# me433_2019_pic32.net
KiCad netlist of a schematic drawn in EAGLE
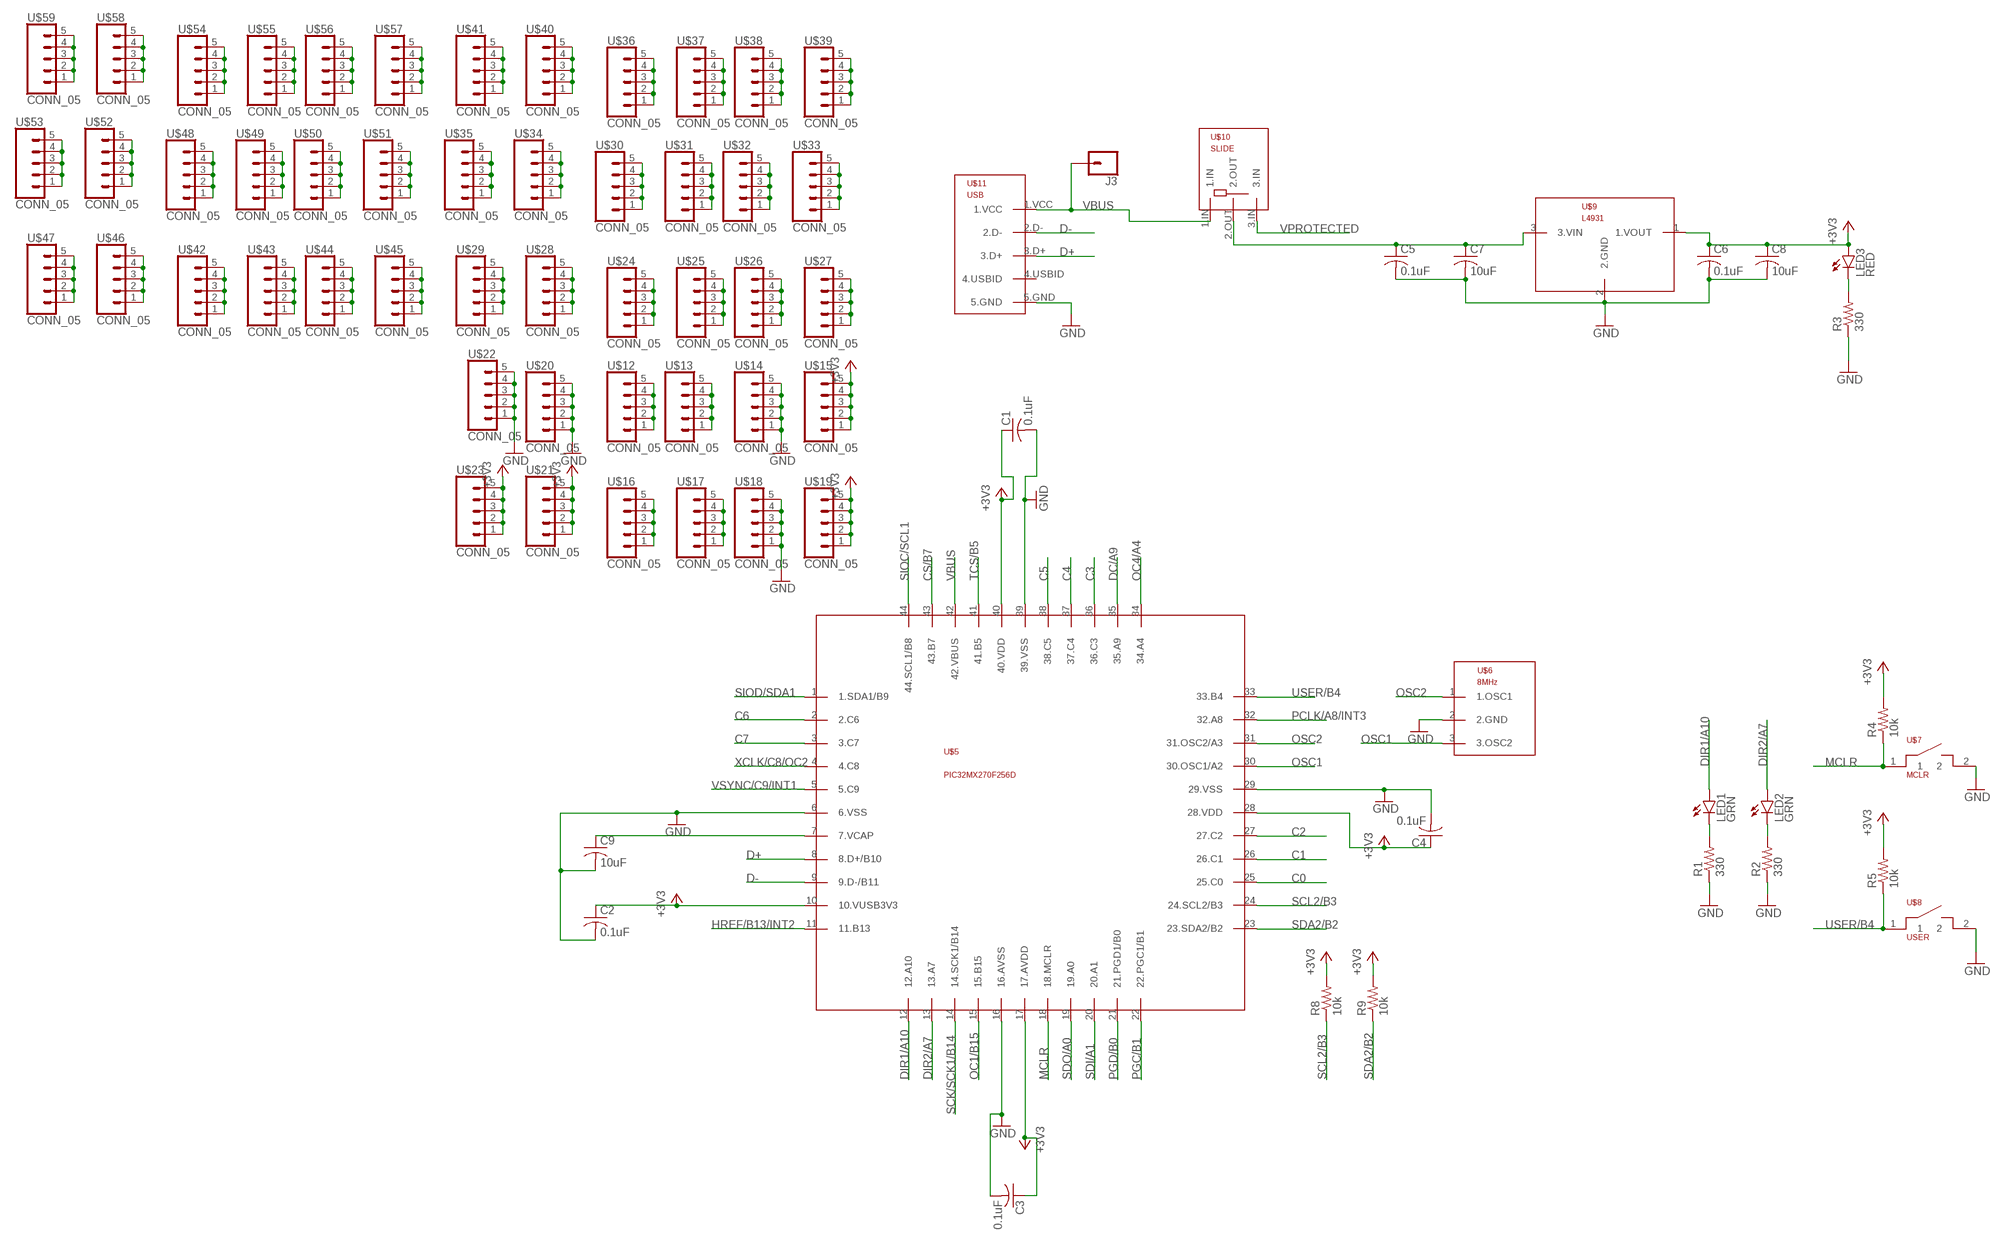
[diagram p0: schematic, sheet 1, part 1 of 2]
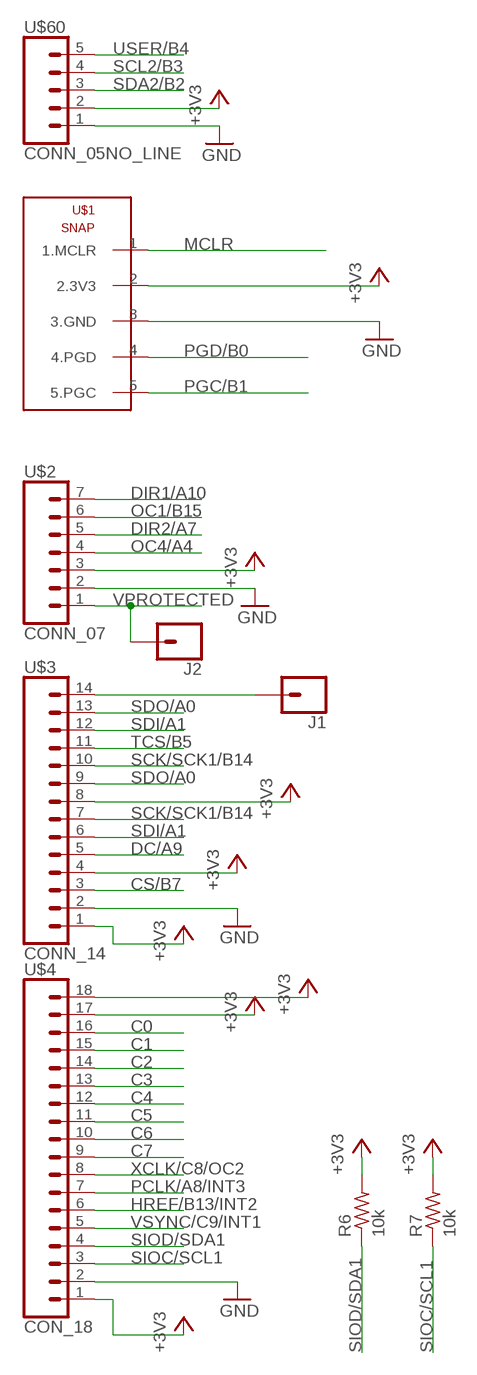
[diagram p1: schematic, sheet 1, part 2 of 2]

(export (version "E")
  (design (tool "Eeschema 10.0.6"))
  (components
    (comp (ref "C1")
      (value "0.1uF")
      (footprint "eagle-import:C025-030X050")
      (libsource (lib "eagle-import") (part "C-US025-030X050"))
    )
    (comp (ref "C2")
      (value "0.1uF")
      (footprint "eagle-import:C025-030X050")
      (libsource (lib "eagle-import") (part "C-US025-030X050"))
    )
    (comp (ref "C3")
      (value "0.1uF")
      (footprint "eagle-import:C025-030X050")
      (libsource (lib "eagle-import") (part "C-US025-030X050"))
    )
    (comp (ref "C4")
      (value "0.1uF")
      (footprint "eagle-import:C025-030X050")
      (libsource (lib "eagle-import") (part "C-US025-030X050"))
    )
    (comp (ref "C5")
      (value "0.1uF")
      (footprint "eagle-import:C025-030X050")
      (libsource (lib "eagle-import") (part "C-US025-030X050"))
    )
    (comp (ref "C6")
      (value "0.1uF")
      (footprint "eagle-import:C025-030X050")
      (libsource (lib "eagle-import") (part "C-US025-030X050"))
    )
    (comp (ref "C7")
      (value "10uF")
      (footprint "eagle-import:C025-030X050")
      (libsource (lib "eagle-import") (part "C-US025-030X050"))
    )
    (comp (ref "C8")
      (value "10uF")
      (footprint "eagle-import:C025-030X050")
      (libsource (lib "eagle-import") (part "C-US025-030X050"))
    )
    (comp (ref "C9")
      (value "10uF")
      (footprint "eagle-import:C025-030X050")
      (libsource (lib "eagle-import") (part "C-US025-030X050"))
    )
    (comp (ref "J1")
      (value "CONN_01")
      (footprint "eagle-import:1X01")
      (libsource (lib "eagle-import") (part "CONN_01"))
    )
    (comp (ref "J2")
      (value "CONN_01")
      (footprint "eagle-import:1X01")
      (libsource (lib "eagle-import") (part "CONN_01"))
    )
    (comp (ref "J3")
      (value "CONN_01")
      (footprint "eagle-import:1X01")
      (libsource (lib "eagle-import") (part "CONN_01"))
    )
    (comp (ref "LED1")
      (value "GRN")
      (footprint "eagle-import:LED3MM")
      (libsource (lib "eagle-import") (part "LED3MM"))
    )
    (comp (ref "LED2")
      (value "GRN")
      (footprint "eagle-import:LED3MM")
      (libsource (lib "eagle-import") (part "LED3MM"))
    )
    (comp (ref "LED3")
      (value "RED")
      (footprint "eagle-import:LED3MM")
      (libsource (lib "eagle-import") (part "LED3MM"))
    )
    (comp (ref "R1")
      (value "330")
      (footprint "eagle-import:0207_10")
      (libsource (lib "eagle-import") (part "R-US_0207/10"))
    )
    (comp (ref "R2")
      (value "330")
      (footprint "eagle-import:0207_10")
      (libsource (lib "eagle-import") (part "R-US_0207/10"))
    )
    (comp (ref "R3")
      (value "330")
      (footprint "eagle-import:0207_10")
      (libsource (lib "eagle-import") (part "R-US_0207/10"))
    )
    (comp (ref "R4")
      (value "10k")
      (footprint "eagle-import:0207_10")
      (libsource (lib "eagle-import") (part "R-US_0207/10"))
    )
    (comp (ref "R5")
      (value "10k")
      (footprint "eagle-import:0207_10")
      (libsource (lib "eagle-import") (part "R-US_0207/10"))
    )
    (comp (ref "R6")
      (value "10k")
      (footprint "eagle-import:0207_10")
      (libsource (lib "eagle-import") (part "R-US_0207/10"))
    )
    (comp (ref "R7")
      (value "10k")
      (footprint "eagle-import:0207_10")
      (libsource (lib "eagle-import") (part "R-US_0207/10"))
    )
    (comp (ref "R8")
      (value "10k")
      (footprint "eagle-import:0207_10")
      (libsource (lib "eagle-import") (part "R-US_0207/10"))
    )
    (comp (ref "R9")
      (value "10k")
      (footprint "eagle-import:0207_10")
      (libsource (lib "eagle-import") (part "R-US_0207/10"))
    )
    (comp (ref "U$1")
      (value "SNAP")
      (footprint "eagle-import:SNAP")
      (libsource (lib "eagle-import") (part "SNAPSNAP"))
    )
    (comp (ref "U$2")
      (value "CONN_07")
      (footprint "eagle-import:1X07")
      (libsource (lib "eagle-import") (part "CONN_07"))
    )
    (comp (ref "U$3")
      (value "CONN_14")
      (footprint "eagle-import:1X14")
      (libsource (lib "eagle-import") (part "CONN_14"))
    )
    (comp (ref "U$4")
      (value "CON_18")
      (footprint "eagle-import:1X18")
      (libsource (lib "eagle-import") (part "CON_18"))
    )
    (comp (ref "U$5")
      (value "PIC32MX270F256D")
      (footprint "eagle-import:TQFP44")
      (libsource (lib "eagle-import") (part "PIC32MX270F256D"))
    )
    (comp (ref "U$6")
      (value "8MHz")
      (footprint "eagle-import:OSC")
      (libsource (lib "eagle-import") (part "OSC"))
    )
    (comp (ref "U$7")
      (value "MCLR")
      (footprint "eagle-import:PB")
      (libsource (lib "eagle-import") (part "PB"))
    )
    (comp (ref "U$8")
      (value "USER")
      (footprint "eagle-import:PB")
      (libsource (lib "eagle-import") (part "PB"))
    )
    (comp (ref "U$9")
      (value "L4931")
      (footprint "eagle-import:L4931")
      (libsource (lib "eagle-import") (part "L4931"))
    )
    (comp (ref "U$10")
      (value "SLIDE")
      (footprint "eagle-import:SLIDE")
      (libsource (lib "eagle-import") (part "SLIDE"))
    )
    (comp (ref "U$11")
      (value "USB")
      (footprint "eagle-import:USB")
      (libsource (lib "eagle-import") (part "USB"))
    )
    (comp (ref "U$12")
      (value "CONN_05")
      (footprint "eagle-import:1X05")
      (libsource (lib "eagle-import") (part "CONN_05"))
    )
    (comp (ref "U$13")
      (value "CONN_05")
      (footprint "eagle-import:1X05")
      (libsource (lib "eagle-import") (part "CONN_05"))
    )
    (comp (ref "U$14")
      (value "CONN_05")
      (footprint "eagle-import:1X05")
      (libsource (lib "eagle-import") (part "CONN_05"))
    )
    (comp (ref "U$15")
      (value "CONN_05")
      (footprint "eagle-import:1X05")
      (libsource (lib "eagle-import") (part "CONN_05"))
    )
    (comp (ref "U$16")
      (value "CONN_05")
      (footprint "eagle-import:1X05")
      (libsource (lib "eagle-import") (part "CONN_05"))
    )
    (comp (ref "U$17")
      (value "CONN_05")
      (footprint "eagle-import:1X05")
      (libsource (lib "eagle-import") (part "CONN_05"))
    )
    (comp (ref "U$18")
      (value "CONN_05")
      (footprint "eagle-import:1X05")
      (libsource (lib "eagle-import") (part "CONN_05"))
    )
    (comp (ref "U$19")
      (value "CONN_05")
      (footprint "eagle-import:1X05")
      (libsource (lib "eagle-import") (part "CONN_05"))
    )
    (comp (ref "U$20")
      (value "CONN_05")
      (footprint "eagle-import:1X05")
      (libsource (lib "eagle-import") (part "CONN_05"))
    )
    (comp (ref "U$21")
      (value "CONN_05")
      (footprint "eagle-import:1X05")
      (libsource (lib "eagle-import") (part "CONN_05"))
    )
    (comp (ref "U$22")
      (value "CONN_05")
      (footprint "eagle-import:1X05")
      (libsource (lib "eagle-import") (part "CONN_05"))
    )
    (comp (ref "U$23")
      (value "CONN_05")
      (footprint "eagle-import:1X05")
      (libsource (lib "eagle-import") (part "CONN_05"))
    )
    (comp (ref "U$24")
      (value "CONN_05")
      (footprint "eagle-import:1X05")
      (libsource (lib "eagle-import") (part "CONN_05"))
    )
    (comp (ref "U$25")
      (value "CONN_05")
      (footprint "eagle-import:1X05")
      (libsource (lib "eagle-import") (part "CONN_05"))
    )
    (comp (ref "U$26")
      (value "CONN_05")
      (footprint "eagle-import:1X05")
      (libsource (lib "eagle-import") (part "CONN_05"))
    )
    (comp (ref "U$27")
      (value "CONN_05")
      (footprint "eagle-import:1X05")
      (libsource (lib "eagle-import") (part "CONN_05"))
    )
    (comp (ref "U$28")
      (value "CONN_05")
      (footprint "eagle-import:1X05")
      (libsource (lib "eagle-import") (part "CONN_05"))
    )
    (comp (ref "U$29")
      (value "CONN_05")
      (footprint "eagle-import:1X05")
      (libsource (lib "eagle-import") (part "CONN_05"))
    )
    (comp (ref "U$30")
      (value "CONN_05")
      (footprint "eagle-import:1X05")
      (libsource (lib "eagle-import") (part "CONN_05"))
    )
    (comp (ref "U$31")
      (value "CONN_05")
      (footprint "eagle-import:1X05")
      (libsource (lib "eagle-import") (part "CONN_05"))
    )
    (comp (ref "U$32")
      (value "CONN_05")
      (footprint "eagle-import:1X05")
      (libsource (lib "eagle-import") (part "CONN_05"))
    )
    (comp (ref "U$33")
      (value "CONN_05")
      (footprint "eagle-import:1X05")
      (libsource (lib "eagle-import") (part "CONN_05"))
    )
    (comp (ref "U$34")
      (value "CONN_05")
      (footprint "eagle-import:1X05")
      (libsource (lib "eagle-import") (part "CONN_05"))
    )
    (comp (ref "U$35")
      (value "CONN_05")
      (footprint "eagle-import:1X05")
      (libsource (lib "eagle-import") (part "CONN_05"))
    )
    (comp (ref "U$36")
      (value "CONN_05")
      (footprint "eagle-import:1X05")
      (libsource (lib "eagle-import") (part "CONN_05"))
    )
    (comp (ref "U$37")
      (value "CONN_05")
      (footprint "eagle-import:1X05")
      (libsource (lib "eagle-import") (part "CONN_05"))
    )
    (comp (ref "U$38")
      (value "CONN_05")
      (footprint "eagle-import:1X05")
      (libsource (lib "eagle-import") (part "CONN_05"))
    )
    (comp (ref "U$39")
      (value "CONN_05")
      (footprint "eagle-import:1X05")
      (libsource (lib "eagle-import") (part "CONN_05"))
    )
    (comp (ref "U$40")
      (value "CONN_05")
      (footprint "eagle-import:1X05")
      (libsource (lib "eagle-import") (part "CONN_05"))
    )
    (comp (ref "U$41")
      (value "CONN_05")
      (footprint "eagle-import:1X05")
      (libsource (lib "eagle-import") (part "CONN_05"))
    )
    (comp (ref "U$42")
      (value "CONN_05")
      (footprint "eagle-import:1X05")
      (libsource (lib "eagle-import") (part "CONN_05"))
    )
    (comp (ref "U$43")
      (value "CONN_05")
      (footprint "eagle-import:1X05")
      (libsource (lib "eagle-import") (part "CONN_05"))
    )
    (comp (ref "U$44")
      (value "CONN_05")
      (footprint "eagle-import:1X05")
      (libsource (lib "eagle-import") (part "CONN_05"))
    )
    (comp (ref "U$45")
      (value "CONN_05")
      (footprint "eagle-import:1X05")
      (libsource (lib "eagle-import") (part "CONN_05"))
    )
    (comp (ref "U$46")
      (value "CONN_05")
      (footprint "eagle-import:1X05")
      (libsource (lib "eagle-import") (part "CONN_05"))
    )
    (comp (ref "U$47")
      (value "CONN_05")
      (footprint "eagle-import:1X05")
      (libsource (lib "eagle-import") (part "CONN_05"))
    )
    (comp (ref "U$48")
      (value "CONN_05")
      (footprint "eagle-import:1X05")
      (libsource (lib "eagle-import") (part "CONN_05"))
    )
    (comp (ref "U$49")
      (value "CONN_05")
      (footprint "eagle-import:1X05")
      (libsource (lib "eagle-import") (part "CONN_05"))
    )
    (comp (ref "U$50")
      (value "CONN_05")
      (footprint "eagle-import:1X05")
      (libsource (lib "eagle-import") (part "CONN_05"))
    )
    (comp (ref "U$51")
      (value "CONN_05")
      (footprint "eagle-import:1X05")
      (libsource (lib "eagle-import") (part "CONN_05"))
    )
    (comp (ref "U$52")
      (value "CONN_05")
      (footprint "eagle-import:1X05")
      (libsource (lib "eagle-import") (part "CONN_05"))
    )
    (comp (ref "U$53")
      (value "CONN_05")
      (footprint "eagle-import:1X05")
      (libsource (lib "eagle-import") (part "CONN_05"))
    )
    (comp (ref "U$54")
      (value "CONN_05")
      (footprint "eagle-import:1X05")
      (libsource (lib "eagle-import") (part "CONN_05"))
    )
    (comp (ref "U$55")
      (value "CONN_05")
      (footprint "eagle-import:1X05")
      (libsource (lib "eagle-import") (part "CONN_05"))
    )
    (comp (ref "U$56")
      (value "CONN_05")
      (footprint "eagle-import:1X05")
      (libsource (lib "eagle-import") (part "CONN_05"))
    )
    (comp (ref "U$57")
      (value "CONN_05")
      (footprint "eagle-import:1X05")
      (libsource (lib "eagle-import") (part "CONN_05"))
    )
    (comp (ref "U$58")
      (value "CONN_05")
      (footprint "eagle-import:1X05")
      (libsource (lib "eagle-import") (part "CONN_05"))
    )
    (comp (ref "U$59")
      (value "CONN_05")
      (footprint "eagle-import:1X05")
      (libsource (lib "eagle-import") (part "CONN_05"))
    )
    (comp (ref "U$60")
      (value "CONN_05NO_LINE")
      (footprint "eagle-import:1X05_NO_LINE")
      (libsource (lib "eagle-import") (part "CONN_05NO_LINE"))
    )
  )
  (nets
    (net (code "1") (name "+3V3") (class "Default")
      (node (ref "C1") (pin "1") (pinfunction "1_1") (pintype "passive"))
      (node (ref "C2") (pin "1") (pinfunction "1_1") (pintype "passive"))
      (node (ref "C3") (pin "1") (pinfunction "1_1") (pintype "passive"))
      (node (ref "C4") (pin "1") (pinfunction "1_1") (pintype "passive"))
      (node (ref "C6") (pin "1") (pinfunction "1_1") (pintype "passive"))
      (node (ref "C8") (pin "1") (pinfunction "1_1") (pintype "passive"))
      (node (ref "LED3") (pin "A") (pinfunction "A_A") (pintype "passive"))
      (node (ref "R4") (pin "2") (pinfunction "2_2") (pintype "passive"))
      (node (ref "R5") (pin "2") (pinfunction "2_2") (pintype "passive"))
      (node (ref "R6") (pin "2") (pinfunction "2_2") (pintype "passive"))
      (node (ref "R7") (pin "2") (pinfunction "2_2") (pintype "passive"))
      (node (ref "R8") (pin "2") (pinfunction "2_2") (pintype "passive"))
      (node (ref "R9") (pin "2") (pinfunction "2_2") (pintype "passive"))
      (node (ref "U$1") (pin "2") (pinfunction "2.3V3_2") (pintype "bidirectional"))
      (node (ref "U$15") (pin "1") (pinfunction "1_1") (pintype "passive"))
      (node (ref "U$15") (pin "2") (pinfunction "2_2") (pintype "passive"))
      (node (ref "U$15") (pin "3") (pinfunction "3_3") (pintype "passive"))
      (node (ref "U$15") (pin "4") (pinfunction "4_4") (pintype "passive"))
      (node (ref "U$15") (pin "5") (pinfunction "5_5") (pintype "passive"))
      (node (ref "U$19") (pin "1") (pinfunction "1_1") (pintype "passive"))
      (node (ref "U$19") (pin "2") (pinfunction "2_2") (pintype "passive"))
      (node (ref "U$19") (pin "3") (pinfunction "3_3") (pintype "passive"))
      (node (ref "U$19") (pin "4") (pinfunction "4_4") (pintype "passive"))
      (node (ref "U$19") (pin "5") (pinfunction "5_5") (pintype "passive"))
      (node (ref "U$2") (pin "3") (pinfunction "3_3") (pintype "passive"))
      (node (ref "U$21") (pin "1") (pinfunction "1_1") (pintype "passive"))
      (node (ref "U$21") (pin "2") (pinfunction "2_2") (pintype "passive"))
      (node (ref "U$21") (pin "3") (pinfunction "3_3") (pintype "passive"))
      (node (ref "U$21") (pin "4") (pinfunction "4_4") (pintype "passive"))
      (node (ref "U$21") (pin "5") (pinfunction "5_5") (pintype "passive"))
      (node (ref "U$23") (pin "1") (pinfunction "1_1") (pintype "passive"))
      (node (ref "U$23") (pin "2") (pinfunction "2_2") (pintype "passive"))
      (node (ref "U$23") (pin "3") (pinfunction "3_3") (pintype "passive"))
      (node (ref "U$23") (pin "4") (pinfunction "4_4") (pintype "passive"))
      (node (ref "U$23") (pin "5") (pinfunction "5_5") (pintype "passive"))
      (node (ref "U$3") (pin "1") (pinfunction "1_1") (pintype "passive"))
      (node (ref "U$3") (pin "4") (pinfunction "4_4") (pintype "passive"))
      (node (ref "U$3") (pin "8") (pinfunction "8_8") (pintype "passive"))
      (node (ref "U$4") (pin "1") (pinfunction "1_1") (pintype "passive"))
      (node (ref "U$4") (pin "17") (pinfunction "17_17") (pintype "passive"))
      (node (ref "U$4") (pin "18") (pinfunction "18_18") (pintype "passive"))
      (node (ref "U$5") (pin "10") (pinfunction "10.VUSB3V3_10") (pintype "bidirectional"))
      (node (ref "U$5") (pin "17") (pinfunction "17.AVDD_17") (pintype "bidirectional"))
      (node (ref "U$5") (pin "28") (pinfunction "28.VDD_28") (pintype "bidirectional"))
      (node (ref "U$5") (pin "40") (pinfunction "40.VDD_40") (pintype "bidirectional"))
      (node (ref "U$60") (pin "2") (pinfunction "2_2") (pintype "passive"))
      (node (ref "U$9") (pin "1") (pinfunction "1.VOUT_1") (pintype "bidirectional"))
    )
    (net (code "2") (name "/C0") (class "Default")
      (node (ref "U$4") (pin "16") (pinfunction "16_16") (pintype "passive"))
      (node (ref "U$5") (pin "25") (pinfunction "25.C0_25") (pintype "bidirectional"))
    )
    (net (code "3") (name "/C1") (class "Default")
      (node (ref "U$4") (pin "15") (pinfunction "15_15") (pintype "passive"))
      (node (ref "U$5") (pin "26") (pinfunction "26.C1_26") (pintype "bidirectional"))
    )
    (net (code "4") (name "/C2") (class "Default")
      (node (ref "U$4") (pin "14") (pinfunction "14_14") (pintype "passive"))
      (node (ref "U$5") (pin "27") (pinfunction "27.C2_27") (pintype "bidirectional"))
    )
    (net (code "5") (name "/C3") (class "Default")
      (node (ref "U$4") (pin "13") (pinfunction "13_13") (pintype "passive"))
      (node (ref "U$5") (pin "36") (pinfunction "36.C3_36") (pintype "bidirectional"))
    )
    (net (code "6") (name "/C4") (class "Default")
      (node (ref "U$4") (pin "12") (pinfunction "12_12") (pintype "passive"))
      (node (ref "U$5") (pin "37") (pinfunction "37.C4_37") (pintype "bidirectional"))
    )
    (net (code "7") (name "/C5") (class "Default")
      (node (ref "U$4") (pin "11") (pinfunction "11_11") (pintype "passive"))
      (node (ref "U$5") (pin "38") (pinfunction "38.C5_38") (pintype "bidirectional"))
    )
    (net (code "8") (name "/C6") (class "Default")
      (node (ref "U$4") (pin "10") (pinfunction "10_10") (pintype "passive"))
      (node (ref "U$5") (pin "2") (pinfunction "2.C6_2") (pintype "bidirectional"))
    )
    (net (code "9") (name "/C7") (class "Default")
      (node (ref "U$4") (pin "9") (pinfunction "9_9") (pintype "passive"))
      (node (ref "U$5") (pin "3") (pinfunction "3.C7_3") (pintype "bidirectional"))
    )
    (net (code "10") (name "/CS{slash}B7") (class "Default")
      (node (ref "U$3") (pin "3") (pinfunction "3_3") (pintype "passive"))
      (node (ref "U$5") (pin "43") (pinfunction "43.B7_43") (pintype "bidirectional"))
    )
    (net (code "11") (name "/D+") (class "Default")
      (node (ref "U$11") (pin "3.D+") (pinfunction "3.D+_3.D+") (pintype "bidirectional"))
      (node (ref "U$5") (pin "8") (pinfunction "8.D+/B10_8") (pintype "bidirectional"))
    )
    (net (code "12") (name "/D-") (class "Default")
      (node (ref "U$11") (pin "2.D-") (pinfunction "2.D-_2.D-") (pintype "bidirectional"))
      (node (ref "U$5") (pin "9") (pinfunction "9.D-/B11_9") (pintype "bidirectional"))
    )
    (net (code "13") (name "/DC{slash}A9") (class "Default")
      (node (ref "U$3") (pin "5") (pinfunction "5_5") (pintype "passive"))
      (node (ref "U$5") (pin "35") (pinfunction "35.A9_35") (pintype "bidirectional"))
    )
    (net (code "14") (name "/DIR1{slash}A10") (class "Default")
      (node (ref "LED1") (pin "A") (pinfunction "A_A") (pintype "passive"))
      (node (ref "U$2") (pin "7") (pinfunction "7_7") (pintype "passive"))
      (node (ref "U$5") (pin "12") (pinfunction "12.A10_12") (pintype "bidirectional"))
    )
    (net (code "15") (name "/DIR2{slash}A7") (class "Default")
      (node (ref "LED2") (pin "A") (pinfunction "A_A") (pintype "passive"))
      (node (ref "U$2") (pin "5") (pinfunction "5_5") (pintype "passive"))
      (node (ref "U$5") (pin "13") (pinfunction "13.A7_13") (pintype "bidirectional"))
    )
    (net (code "16") (name "/HREF{slash}B13{slash}INT2") (class "Default")
      (node (ref "U$4") (pin "6") (pinfunction "6_6") (pintype "passive"))
      (node (ref "U$5") (pin "11") (pinfunction "11.B13_11") (pintype "bidirectional"))
    )
    (net (code "17") (name "/MCLR") (class "Default")
      (node (ref "R4") (pin "1") (pinfunction "1_1") (pintype "passive"))
      (node (ref "U$1") (pin "1") (pinfunction "1.MCLR_1") (pintype "bidirectional"))
      (node (ref "U$5") (pin "18") (pinfunction "18.MCLR_18") (pintype "bidirectional"))
      (node (ref "U$7") (pin "1") (pinfunction "1_1") (pintype "bidirectional"))
    )
    (net (code "18") (name "/OC1{slash}B15") (class "Default")
      (node (ref "U$2") (pin "6") (pinfunction "6_6") (pintype "passive"))
      (node (ref "U$5") (pin "15") (pinfunction "15.B15_15") (pintype "bidirectional"))
    )
    (net (code "19") (name "/OC4{slash}A4") (class "Default")
      (node (ref "U$2") (pin "4") (pinfunction "4_4") (pintype "passive"))
      (node (ref "U$5") (pin "34") (pinfunction "34.A4_34") (pintype "bidirectional"))
    )
    (net (code "20") (name "/OSC1") (class "Default")
      (node (ref "U$5") (pin "30") (pinfunction "30.OSC1/A2_30") (pintype "bidirectional"))
      (node (ref "U$6") (pin "3") (pinfunction "3.OSC2_3") (pintype "bidirectional"))
    )
    (net (code "21") (name "/OSC2") (class "Default")
      (node (ref "U$5") (pin "31") (pinfunction "31.OSC2/A3_31") (pintype "bidirectional"))
      (node (ref "U$6") (pin "1") (pinfunction "1.OSC1_1") (pintype "bidirectional"))
    )
    (net (code "22") (name "/PCLK{slash}A8{slash}INT3") (class "Default")
      (node (ref "U$4") (pin "7") (pinfunction "7_7") (pintype "passive"))
      (node (ref "U$5") (pin "32") (pinfunction "32.A8_32") (pintype "bidirectional"))
    )
    (net (code "23") (name "/PGC{slash}B1") (class "Default")
      (node (ref "U$1") (pin "5") (pinfunction "5.PGC_5") (pintype "bidirectional"))
      (node (ref "U$5") (pin "22") (pinfunction "22.PGC1/B1_22") (pintype "bidirectional"))
    )
    (net (code "24") (name "/PGD{slash}B0") (class "Default")
      (node (ref "U$1") (pin "4") (pinfunction "4.PGD_4") (pintype "bidirectional"))
      (node (ref "U$5") (pin "21") (pinfunction "21.PGD1/B0_21") (pintype "bidirectional"))
    )
    (net (code "25") (name "/SCK{slash}SCK1{slash}B14") (class "Default")
      (node (ref "U$3") (pin "10") (pinfunction "10_10") (pintype "passive"))
      (node (ref "U$3") (pin "7") (pinfunction "7_7") (pintype "passive"))
      (node (ref "U$5") (pin "14") (pinfunction "14.SCK1/B14_14") (pintype "bidirectional"))
    )
    (net (code "26") (name "/SCL2{slash}B3") (class "Default")
      (node (ref "R8") (pin "1") (pinfunction "1_1") (pintype "passive"))
      (node (ref "U$5") (pin "24") (pinfunction "24.SCL2/B3_24") (pintype "bidirectional"))
      (node (ref "U$60") (pin "4") (pinfunction "4_4") (pintype "passive"))
    )
    (net (code "27") (name "/SDA2{slash}B2") (class "Default")
      (node (ref "R9") (pin "1") (pinfunction "1_1") (pintype "passive"))
      (node (ref "U$5") (pin "23") (pinfunction "23.SDA2/B2_23") (pintype "bidirectional"))
      (node (ref "U$60") (pin "3") (pinfunction "3_3") (pintype "passive"))
    )
    (net (code "28") (name "/SDI{slash}A1") (class "Default")
      (node (ref "U$3") (pin "12") (pinfunction "12_12") (pintype "passive"))
      (node (ref "U$3") (pin "6") (pinfunction "6_6") (pintype "passive"))
      (node (ref "U$5") (pin "20") (pinfunction "20.A1_20") (pintype "bidirectional"))
    )
    (net (code "29") (name "/SDO{slash}A0") (class "Default")
      (node (ref "U$3") (pin "13") (pinfunction "13_13") (pintype "passive"))
      (node (ref "U$3") (pin "9") (pinfunction "9_9") (pintype "passive"))
      (node (ref "U$5") (pin "19") (pinfunction "19.A0_19") (pintype "bidirectional"))
    )
    (net (code "30") (name "/SIOC{slash}SCL1") (class "Default")
      (node (ref "R7") (pin "1") (pinfunction "1_1") (pintype "passive"))
      (node (ref "U$4") (pin "3") (pinfunction "3_3") (pintype "passive"))
      (node (ref "U$5") (pin "44") (pinfunction "44.SCL1/B8_44") (pintype "bidirectional"))
    )
    (net (code "31") (name "/SIOD{slash}SDA1") (class "Default")
      (node (ref "R6") (pin "1") (pinfunction "1_1") (pintype "passive"))
      (node (ref "U$4") (pin "4") (pinfunction "4_4") (pintype "passive"))
      (node (ref "U$5") (pin "1") (pinfunction "1.SDA1/B9_1") (pintype "bidirectional"))
    )
    (net (code "32") (name "/TCS{slash}B5") (class "Default")
      (node (ref "U$3") (pin "11") (pinfunction "11_11") (pintype "passive"))
      (node (ref "U$5") (pin "41") (pinfunction "41.B5_41") (pintype "bidirectional"))
    )
    (net (code "33") (name "/USER{slash}B4") (class "Default")
      (node (ref "R5") (pin "1") (pinfunction "1_1") (pintype "passive"))
      (node (ref "U$5") (pin "33") (pinfunction "33.B4_33") (pintype "bidirectional"))
      (node (ref "U$60") (pin "5") (pinfunction "5_5") (pintype "passive"))
      (node (ref "U$8") (pin "1") (pinfunction "1_1") (pintype "bidirectional"))
    )
    (net (code "34") (name "/VBUS") (class "Default")
      (node (ref "J3") (pin "1") (pinfunction "1_1") (pintype "passive"))
      (node (ref "U$10") (pin "1.IN") (pinfunction "1.IN_1.IN") (pintype "bidirectional"))
      (node (ref "U$11") (pin "1.VCC") (pinfunction "1.VCC_1.VCC") (pintype "bidirectional"))
      (node (ref "U$5") (pin "42") (pinfunction "42.VBUS_42") (pintype "bidirectional"))
    )
    (net (code "35") (name "/VPROTECTED") (class "Default")
      (node (ref "J2") (pin "1") (pinfunction "1_1") (pintype "passive"))
      (node (ref "U$10") (pin "3.IN") (pinfunction "3.IN_3.IN") (pintype "bidirectional"))
      (node (ref "U$2") (pin "1") (pinfunction "1_1") (pintype "passive"))
    )
    (net (code "36") (name "/VSYNC{slash}C9{slash}INT1") (class "Default")
      (node (ref "U$4") (pin "5") (pinfunction "5_5") (pintype "passive"))
      (node (ref "U$5") (pin "5") (pinfunction "5.C9_5") (pintype "bidirectional"))
    )
    (net (code "37") (name "/XCLK{slash}C8{slash}OC2") (class "Default")
      (node (ref "U$4") (pin "8") (pinfunction "8_8") (pintype "passive"))
      (node (ref "U$5") (pin "4") (pinfunction "4.C8_4") (pintype "bidirectional"))
    )
    (net (code "38") (name "GND") (class "Default")
      (node (ref "C1") (pin "2") (pinfunction "2_2") (pintype "passive"))
      (node (ref "C2") (pin "2") (pinfunction "2_2") (pintype "passive"))
      (node (ref "C3") (pin "2") (pinfunction "2_2") (pintype "passive"))
      (node (ref "C4") (pin "2") (pinfunction "2_2") (pintype "passive"))
      (node (ref "C5") (pin "2") (pinfunction "2_2") (pintype "passive"))
      (node (ref "C6") (pin "2") (pinfunction "2_2") (pintype "passive"))
      (node (ref "C7") (pin "2") (pinfunction "2_2") (pintype "passive"))
      (node (ref "C8") (pin "2") (pinfunction "2_2") (pintype "passive"))
      (node (ref "C9") (pin "2") (pinfunction "2_2") (pintype "passive"))
      (node (ref "R1") (pin "1") (pinfunction "1_1") (pintype "passive"))
      (node (ref "R2") (pin "1") (pinfunction "1_1") (pintype "passive"))
      (node (ref "R3") (pin "1") (pinfunction "1_1") (pintype "passive"))
      (node (ref "U$1") (pin "3") (pinfunction "3.GND_3") (pintype "bidirectional"))
      (node (ref "U$11") (pin "5.GND") (pinfunction "5.GND_5.GND") (pintype "bidirectional"))
      (node (ref "U$14") (pin "1") (pinfunction "1_1") (pintype "passive"))
      (node (ref "U$14") (pin "2") (pinfunction "2_2") (pintype "passive"))
      (node (ref "U$14") (pin "3") (pinfunction "3_3") (pintype "passive"))
      (node (ref "U$14") (pin "4") (pinfunction "4_4") (pintype "passive"))
      (node (ref "U$14") (pin "5") (pinfunction "5_5") (pintype "passive"))
      (node (ref "U$18") (pin "1") (pinfunction "1_1") (pintype "passive"))
      (node (ref "U$18") (pin "2") (pinfunction "2_2") (pintype "passive"))
      (node (ref "U$18") (pin "3") (pinfunction "3_3") (pintype "passive"))
      (node (ref "U$18") (pin "4") (pinfunction "4_4") (pintype "passive"))
      (node (ref "U$18") (pin "5") (pinfunction "5_5") (pintype "passive"))
      (node (ref "U$2") (pin "2") (pinfunction "2_2") (pintype "passive"))
      (node (ref "U$20") (pin "1") (pinfunction "1_1") (pintype "passive"))
      (node (ref "U$20") (pin "2") (pinfunction "2_2") (pintype "passive"))
      (node (ref "U$20") (pin "3") (pinfunction "3_3") (pintype "passive"))
      (node (ref "U$20") (pin "4") (pinfunction "4_4") (pintype "passive"))
      (node (ref "U$20") (pin "5") (pinfunction "5_5") (pintype "passive"))
      (node (ref "U$22") (pin "1") (pinfunction "1_1") (pintype "passive"))
      (node (ref "U$22") (pin "2") (pinfunction "2_2") (pintype "passive"))
      (node (ref "U$22") (pin "3") (pinfunction "3_3") (pintype "passive"))
      (node (ref "U$22") (pin "4") (pinfunction "4_4") (pintype "passive"))
      (node (ref "U$22") (pin "5") (pinfunction "5_5") (pintype "passive"))
      (node (ref "U$3") (pin "2") (pinfunction "2_2") (pintype "passive"))
      (node (ref "U$4") (pin "2") (pinfunction "2_2") (pintype "passive"))
      (node (ref "U$5") (pin "16") (pinfunction "16.AVSS_16") (pintype "bidirectional"))
      (node (ref "U$5") (pin "29") (pinfunction "29.VSS_29") (pintype "bidirectional"))
      (node (ref "U$5") (pin "39") (pinfunction "39.VSS_39") (pintype "bidirectional"))
      (node (ref "U$5") (pin "6") (pinfunction "6.VSS_6") (pintype "bidirectional"))
      (node (ref "U$6") (pin "2") (pinfunction "2.GND_2") (pintype "bidirectional"))
      (node (ref "U$60") (pin "1") (pinfunction "1_1") (pintype "passive"))
      (node (ref "U$7") (pin "2") (pinfunction "2_2") (pintype "bidirectional"))
      (node (ref "U$8") (pin "2") (pinfunction "2_2") (pintype "bidirectional"))
      (node (ref "U$9") (pin "2") (pinfunction "2.GND_2") (pintype "bidirectional"))
    )
    (net (code "39") (name "Net-(J1-Pad1)") (class "Default")
      (node (ref "J1") (pin "1") (pinfunction "1_1") (pintype "passive"))
      (node (ref "U$3") (pin "14") (pinfunction "14_14") (pintype "passive"))
    )
    (net (code "40") (name "Net-(LED1-C)") (class "Default")
      (node (ref "LED1") (pin "K") (pinfunction "C_K") (pintype "passive"))
      (node (ref "R1") (pin "2") (pinfunction "2_2") (pintype "passive"))
    )
    (net (code "41") (name "Net-(LED2-C)") (class "Default")
      (node (ref "LED2") (pin "K") (pinfunction "C_K") (pintype "passive"))
      (node (ref "R2") (pin "2") (pinfunction "2_2") (pintype "passive"))
    )
    (net (code "42") (name "Net-(LED3-C)") (class "Default")
      (node (ref "LED3") (pin "K") (pinfunction "C_K") (pintype "passive"))
      (node (ref "R3") (pin "2") (pinfunction "2_2") (pintype "passive"))
    )
    (net (code "43") (name "Net-(U$5-7.VCAP)") (class "Default")
      (node (ref "C9") (pin "1") (pinfunction "1_1") (pintype "passive"))
      (node (ref "U$5") (pin "7") (pinfunction "7.VCAP_7") (pintype "bidirectional"))
    )
    (net (code "44") (name "Net-(U$9-3.VIN)") (class "Default")
      (node (ref "C5") (pin "1") (pinfunction "1_1") (pintype "passive"))
      (node (ref "C7") (pin "1") (pinfunction "1_1") (pintype "passive"))
      (node (ref "U$10") (pin "2.OUT") (pinfunction "2.OUT_2.OUT") (pintype "bidirectional"))
      (node (ref "U$9") (pin "3") (pinfunction "3.VIN_3") (pintype "bidirectional"))
    )
    (net (code "45") (name "Net-(U$12-Pad1)") (class "Default")
      (node (ref "U$12") (pin "1") (pinfunction "1_1") (pintype "passive"))
      (node (ref "U$12") (pin "2") (pinfunction "2_2") (pintype "passive"))
      (node (ref "U$12") (pin "3") (pinfunction "3_3") (pintype "passive"))
      (node (ref "U$12") (pin "4") (pinfunction "4_4") (pintype "passive"))
      (node (ref "U$12") (pin "5") (pinfunction "5_5") (pintype "passive"))
    )
    (net (code "46") (name "Net-(U$13-Pad1)") (class "Default")
      (node (ref "U$13") (pin "1") (pinfunction "1_1") (pintype "passive"))
      (node (ref "U$13") (pin "2") (pinfunction "2_2") (pintype "passive"))
      (node (ref "U$13") (pin "3") (pinfunction "3_3") (pintype "passive"))
      (node (ref "U$13") (pin "4") (pinfunction "4_4") (pintype "passive"))
      (node (ref "U$13") (pin "5") (pinfunction "5_5") (pintype "passive"))
    )
    (net (code "47") (name "Net-(U$16-Pad1)") (class "Default")
      (node (ref "U$16") (pin "1") (pinfunction "1_1") (pintype "passive"))
      (node (ref "U$16") (pin "2") (pinfunction "2_2") (pintype "passive"))
      (node (ref "U$16") (pin "3") (pinfunction "3_3") (pintype "passive"))
      (node (ref "U$16") (pin "4") (pinfunction "4_4") (pintype "passive"))
      (node (ref "U$16") (pin "5") (pinfunction "5_5") (pintype "passive"))
    )
    (net (code "48") (name "Net-(U$17-Pad1)") (class "Default")
      (node (ref "U$17") (pin "1") (pinfunction "1_1") (pintype "passive"))
      (node (ref "U$17") (pin "2") (pinfunction "2_2") (pintype "passive"))
      (node (ref "U$17") (pin "3") (pinfunction "3_3") (pintype "passive"))
      (node (ref "U$17") (pin "4") (pinfunction "4_4") (pintype "passive"))
      (node (ref "U$17") (pin "5") (pinfunction "5_5") (pintype "passive"))
    )
    (net (code "49") (name "Net-(U$24-Pad1)") (class "Default")
      (node (ref "U$24") (pin "1") (pinfunction "1_1") (pintype "passive"))
      (node (ref "U$24") (pin "2") (pinfunction "2_2") (pintype "passive"))
      (node (ref "U$24") (pin "3") (pinfunction "3_3") (pintype "passive"))
      (node (ref "U$24") (pin "4") (pinfunction "4_4") (pintype "passive"))
      (node (ref "U$24") (pin "5") (pinfunction "5_5") (pintype "passive"))
    )
    (net (code "50") (name "Net-(U$25-Pad1)") (class "Default")
      (node (ref "U$25") (pin "1") (pinfunction "1_1") (pintype "passive"))
      (node (ref "U$25") (pin "2") (pinfunction "2_2") (pintype "passive"))
      (node (ref "U$25") (pin "3") (pinfunction "3_3") (pintype "passive"))
      (node (ref "U$25") (pin "4") (pinfunction "4_4") (pintype "passive"))
      (node (ref "U$25") (pin "5") (pinfunction "5_5") (pintype "passive"))
    )
    (net (code "51") (name "Net-(U$26-Pad1)") (class "Default")
      (node (ref "U$26") (pin "1") (pinfunction "1_1") (pintype "passive"))
      (node (ref "U$26") (pin "2") (pinfunction "2_2") (pintype "passive"))
      (node (ref "U$26") (pin "3") (pinfunction "3_3") (pintype "passive"))
      (node (ref "U$26") (pin "4") (pinfunction "4_4") (pintype "passive"))
      (node (ref "U$26") (pin "5") (pinfunction "5_5") (pintype "passive"))
    )
    (net (code "52") (name "Net-(U$27-Pad1)") (class "Default")
      (node (ref "U$27") (pin "1") (pinfunction "1_1") (pintype "passive"))
      (node (ref "U$27") (pin "2") (pinfunction "2_2") (pintype "passive"))
      (node (ref "U$27") (pin "3") (pinfunction "3_3") (pintype "passive"))
      (node (ref "U$27") (pin "4") (pinfunction "4_4") (pintype "passive"))
      (node (ref "U$27") (pin "5") (pinfunction "5_5") (pintype "passive"))
    )
    (net (code "53") (name "Net-(U$28-Pad1)") (class "Default")
      (node (ref "U$28") (pin "1") (pinfunction "1_1") (pintype "passive"))
      (node (ref "U$28") (pin "2") (pinfunction "2_2") (pintype "passive"))
      (node (ref "U$28") (pin "3") (pinfunction "3_3") (pintype "passive"))
      (node (ref "U$28") (pin "4") (pinfunction "4_4") (pintype "passive"))
      (node (ref "U$28") (pin "5") (pinfunction "5_5") (pintype "passive"))
    )
    (net (code "54") (name "Net-(U$29-Pad1)") (class "Default")
      (node (ref "U$29") (pin "1") (pinfunction "1_1") (pintype "passive"))
      (node (ref "U$29") (pin "2") (pinfunction "2_2") (pintype "passive"))
      (node (ref "U$29") (pin "3") (pinfunction "3_3") (pintype "passive"))
      (node (ref "U$29") (pin "4") (pinfunction "4_4") (pintype "passive"))
      (node (ref "U$29") (pin "5") (pinfunction "5_5") (pintype "passive"))
    )
    (net (code "55") (name "Net-(U$30-Pad1)") (class "Default")
      (node (ref "U$30") (pin "1") (pinfunction "1_1") (pintype "passive"))
      (node (ref "U$30") (pin "2") (pinfunction "2_2") (pintype "passive"))
      (node (ref "U$30") (pin "3") (pinfunction "3_3") (pintype "passive"))
      (node (ref "U$30") (pin "4") (pinfunction "4_4") (pintype "passive"))
      (node (ref "U$30") (pin "5") (pinfunction "5_5") (pintype "passive"))
    )
    (net (code "56") (name "Net-(U$31-Pad1)") (class "Default")
      (node (ref "U$31") (pin "1") (pinfunction "1_1") (pintype "passive"))
      (node (ref "U$31") (pin "2") (pinfunction "2_2") (pintype "passive"))
      (node (ref "U$31") (pin "3") (pinfunction "3_3") (pintype "passive"))
      (node (ref "U$31") (pin "4") (pinfunction "4_4") (pintype "passive"))
      (node (ref "U$31") (pin "5") (pinfunction "5_5") (pintype "passive"))
    )
    (net (code "57") (name "Net-(U$32-Pad1)") (class "Default")
      (node (ref "U$32") (pin "1") (pinfunction "1_1") (pintype "passive"))
      (node (ref "U$32") (pin "2") (pinfunction "2_2") (pintype "passive"))
      (node (ref "U$32") (pin "3") (pinfunction "3_3") (pintype "passive"))
      (node (ref "U$32") (pin "4") (pinfunction "4_4") (pintype "passive"))
      (node (ref "U$32") (pin "5") (pinfunction "5_5") (pintype "passive"))
    )
    (net (code "58") (name "Net-(U$33-Pad1)") (class "Default")
      (node (ref "U$33") (pin "1") (pinfunction "1_1") (pintype "passive"))
      (node (ref "U$33") (pin "2") (pinfunction "2_2") (pintype "passive"))
      (node (ref "U$33") (pin "3") (pinfunction "3_3") (pintype "passive"))
      (node (ref "U$33") (pin "4") (pinfunction "4_4") (pintype "passive"))
      (node (ref "U$33") (pin "5") (pinfunction "5_5") (pintype "passive"))
    )
    (net (code "59") (name "Net-(U$34-Pad1)") (class "Default")
      (node (ref "U$34") (pin "1") (pinfunction "1_1") (pintype "passive"))
      (node (ref "U$34") (pin "2") (pinfunction "2_2") (pintype "passive"))
      (node (ref "U$34") (pin "3") (pinfunction "3_3") (pintype "passive"))
      (node (ref "U$34") (pin "4") (pinfunction "4_4") (pintype "passive"))
      (node (ref "U$34") (pin "5") (pinfunction "5_5") (pintype "passive"))
    )
    (net (code "60") (name "Net-(U$35-Pad1)") (class "Default")
      (node (ref "U$35") (pin "1") (pinfunction "1_1") (pintype "passive"))
      (node (ref "U$35") (pin "2") (pinfunction "2_2") (pintype "passive"))
      (node (ref "U$35") (pin "3") (pinfunction "3_3") (pintype "passive"))
      (node (ref "U$35") (pin "4") (pinfunction "4_4") (pintype "passive"))
      (node (ref "U$35") (pin "5") (pinfunction "5_5") (pintype "passive"))
    )
    (net (code "61") (name "Net-(U$36-Pad1)") (class "Default")
      (node (ref "U$36") (pin "1") (pinfunction "1_1") (pintype "passive"))
      (node (ref "U$36") (pin "2") (pinfunction "2_2") (pintype "passive"))
      (node (ref "U$36") (pin "3") (pinfunction "3_3") (pintype "passive"))
      (node (ref "U$36") (pin "4") (pinfunction "4_4") (pintype "passive"))
      (node (ref "U$36") (pin "5") (pinfunction "5_5") (pintype "passive"))
    )
    (net (code "62") (name "Net-(U$37-Pad1)") (class "Default")
      (node (ref "U$37") (pin "1") (pinfunction "1_1") (pintype "passive"))
      (node (ref "U$37") (pin "2") (pinfunction "2_2") (pintype "passive"))
      (node (ref "U$37") (pin "3") (pinfunction "3_3") (pintype "passive"))
      (node (ref "U$37") (pin "4") (pinfunction "4_4") (pintype "passive"))
      (node (ref "U$37") (pin "5") (pinfunction "5_5") (pintype "passive"))
    )
    (net (code "63") (name "Net-(U$38-Pad1)") (class "Default")
      (node (ref "U$38") (pin "1") (pinfunction "1_1") (pintype "passive"))
      (node (ref "U$38") (pin "2") (pinfunction "2_2") (pintype "passive"))
      (node (ref "U$38") (pin "3") (pinfunction "3_3") (pintype "passive"))
      (node (ref "U$38") (pin "4") (pinfunction "4_4") (pintype "passive"))
      (node (ref "U$38") (pin "5") (pinfunction "5_5") (pintype "passive"))
    )
    (net (code "64") (name "Net-(U$39-Pad1)") (class "Default")
      (node (ref "U$39") (pin "1") (pinfunction "1_1") (pintype "passive"))
      (node (ref "U$39") (pin "2") (pinfunction "2_2") (pintype "passive"))
      (node (ref "U$39") (pin "3") (pinfunction "3_3") (pintype "passive"))
      (node (ref "U$39") (pin "4") (pinfunction "4_4") (pintype "passive"))
      (node (ref "U$39") (pin "5") (pinfunction "5_5") (pintype "passive"))
    )
    (net (code "65") (name "Net-(U$40-Pad1)") (class "Default")
      (node (ref "U$40") (pin "1") (pinfunction "1_1") (pintype "passive"))
      (node (ref "U$40") (pin "2") (pinfunction "2_2") (pintype "passive"))
      (node (ref "U$40") (pin "3") (pinfunction "3_3") (pintype "passive"))
      (node (ref "U$40") (pin "4") (pinfunction "4_4") (pintype "passive"))
      (node (ref "U$40") (pin "5") (pinfunction "5_5") (pintype "passive"))
    )
    (net (code "66") (name "Net-(U$41-Pad1)") (class "Default")
      (node (ref "U$41") (pin "1") (pinfunction "1_1") (pintype "passive"))
      (node (ref "U$41") (pin "2") (pinfunction "2_2") (pintype "passive"))
      (node (ref "U$41") (pin "3") (pinfunction "3_3") (pintype "passive"))
      (node (ref "U$41") (pin "4") (pinfunction "4_4") (pintype "passive"))
      (node (ref "U$41") (pin "5") (pinfunction "5_5") (pintype "passive"))
    )
    (net (code "67") (name "Net-(U$42-Pad1)") (class "Default")
      (node (ref "U$42") (pin "1") (pinfunction "1_1") (pintype "passive"))
      (node (ref "U$42") (pin "2") (pinfunction "2_2") (pintype "passive"))
      (node (ref "U$42") (pin "3") (pinfunction "3_3") (pintype "passive"))
      (node (ref "U$42") (pin "4") (pinfunction "4_4") (pintype "passive"))
      (node (ref "U$42") (pin "5") (pinfunction "5_5") (pintype "passive"))
    )
    (net (code "68") (name "Net-(U$43-Pad1)") (class "Default")
      (node (ref "U$43") (pin "1") (pinfunction "1_1") (pintype "passive"))
      (node (ref "U$43") (pin "2") (pinfunction "2_2") (pintype "passive"))
      (node (ref "U$43") (pin "3") (pinfunction "3_3") (pintype "passive"))
      (node (ref "U$43") (pin "4") (pinfunction "4_4") (pintype "passive"))
      (node (ref "U$43") (pin "5") (pinfunction "5_5") (pintype "passive"))
    )
    (net (code "69") (name "Net-(U$44-Pad1)") (class "Default")
      (node (ref "U$44") (pin "1") (pinfunction "1_1") (pintype "passive"))
      (node (ref "U$44") (pin "2") (pinfunction "2_2") (pintype "passive"))
      (node (ref "U$44") (pin "3") (pinfunction "3_3") (pintype "passive"))
      (node (ref "U$44") (pin "4") (pinfunction "4_4") (pintype "passive"))
      (node (ref "U$44") (pin "5") (pinfunction "5_5") (pintype "passive"))
    )
    (net (code "70") (name "Net-(U$45-Pad1)") (class "Default")
      (node (ref "U$45") (pin "1") (pinfunction "1_1") (pintype "passive"))
      (node (ref "U$45") (pin "2") (pinfunction "2_2") (pintype "passive"))
      (node (ref "U$45") (pin "3") (pinfunction "3_3") (pintype "passive"))
      (node (ref "U$45") (pin "4") (pinfunction "4_4") (pintype "passive"))
      (node (ref "U$45") (pin "5") (pinfunction "5_5") (pintype "passive"))
    )
    (net (code "71") (name "Net-(U$46-Pad1)") (class "Default")
      (node (ref "U$46") (pin "1") (pinfunction "1_1") (pintype "passive"))
      (node (ref "U$46") (pin "2") (pinfunction "2_2") (pintype "passive"))
      (node (ref "U$46") (pin "3") (pinfunction "3_3") (pintype "passive"))
      (node (ref "U$46") (pin "4") (pinfunction "4_4") (pintype "passive"))
      (node (ref "U$46") (pin "5") (pinfunction "5_5") (pintype "passive"))
    )
    (net (code "72") (name "Net-(U$47-Pad1)") (class "Default")
      (node (ref "U$47") (pin "1") (pinfunction "1_1") (pintype "passive"))
      (node (ref "U$47") (pin "2") (pinfunction "2_2") (pintype "passive"))
      (node (ref "U$47") (pin "3") (pinfunction "3_3") (pintype "passive"))
      (node (ref "U$47") (pin "4") (pinfunction "4_4") (pintype "passive"))
      (node (ref "U$47") (pin "5") (pinfunction "5_5") (pintype "passive"))
    )
    (net (code "73") (name "Net-(U$48-Pad1)") (class "Default")
      (node (ref "U$48") (pin "1") (pinfunction "1_1") (pintype "passive"))
      (node (ref "U$48") (pin "2") (pinfunction "2_2") (pintype "passive"))
      (node (ref "U$48") (pin "3") (pinfunction "3_3") (pintype "passive"))
      (node (ref "U$48") (pin "4") (pinfunction "4_4") (pintype "passive"))
      (node (ref "U$48") (pin "5") (pinfunction "5_5") (pintype "passive"))
    )
    (net (code "74") (name "Net-(U$49-Pad1)") (class "Default")
      (node (ref "U$49") (pin "1") (pinfunction "1_1") (pintype "passive"))
      (node (ref "U$49") (pin "2") (pinfunction "2_2") (pintype "passive"))
      (node (ref "U$49") (pin "3") (pinfunction "3_3") (pintype "passive"))
      (node (ref "U$49") (pin "4") (pinfunction "4_4") (pintype "passive"))
      (node (ref "U$49") (pin "5") (pinfunction "5_5") (pintype "passive"))
    )
    (net (code "75") (name "Net-(U$50-Pad1)") (class "Default")
      (node (ref "U$50") (pin "1") (pinfunction "1_1") (pintype "passive"))
      (node (ref "U$50") (pin "2") (pinfunction "2_2") (pintype "passive"))
      (node (ref "U$50") (pin "3") (pinfunction "3_3") (pintype "passive"))
      (node (ref "U$50") (pin "4") (pinfunction "4_4") (pintype "passive"))
      (node (ref "U$50") (pin "5") (pinfunction "5_5") (pintype "passive"))
    )
    (net (code "76") (name "Net-(U$51-Pad1)") (class "Default")
      (node (ref "U$51") (pin "1") (pinfunction "1_1") (pintype "passive"))
      (node (ref "U$51") (pin "2") (pinfunction "2_2") (pintype "passive"))
      (node (ref "U$51") (pin "3") (pinfunction "3_3") (pintype "passive"))
      (node (ref "U$51") (pin "4") (pinfunction "4_4") (pintype "passive"))
      (node (ref "U$51") (pin "5") (pinfunction "5_5") (pintype "passive"))
    )
    (net (code "77") (name "Net-(U$52-Pad1)") (class "Default")
      (node (ref "U$52") (pin "1") (pinfunction "1_1") (pintype "passive"))
      (node (ref "U$52") (pin "2") (pinfunction "2_2") (pintype "passive"))
      (node (ref "U$52") (pin "3") (pinfunction "3_3") (pintype "passive"))
      (node (ref "U$52") (pin "4") (pinfunction "4_4") (pintype "passive"))
      (node (ref "U$52") (pin "5") (pinfunction "5_5") (pintype "passive"))
    )
    (net (code "78") (name "Net-(U$53-Pad1)") (class "Default")
      (node (ref "U$53") (pin "1") (pinfunction "1_1") (pintype "passive"))
      (node (ref "U$53") (pin "2") (pinfunction "2_2") (pintype "passive"))
      (node (ref "U$53") (pin "3") (pinfunction "3_3") (pintype "passive"))
      (node (ref "U$53") (pin "4") (pinfunction "4_4") (pintype "passive"))
      (node (ref "U$53") (pin "5") (pinfunction "5_5") (pintype "passive"))
    )
    (net (code "79") (name "Net-(U$54-Pad1)") (class "Default")
      (node (ref "U$54") (pin "1") (pinfunction "1_1") (pintype "passive"))
      (node (ref "U$54") (pin "2") (pinfunction "2_2") (pintype "passive"))
      (node (ref "U$54") (pin "3") (pinfunction "3_3") (pintype "passive"))
      (node (ref "U$54") (pin "4") (pinfunction "4_4") (pintype "passive"))
      (node (ref "U$54") (pin "5") (pinfunction "5_5") (pintype "passive"))
    )
    (net (code "80") (name "Net-(U$55-Pad1)") (class "Default")
      (node (ref "U$55") (pin "1") (pinfunction "1_1") (pintype "passive"))
      (node (ref "U$55") (pin "2") (pinfunction "2_2") (pintype "passive"))
      (node (ref "U$55") (pin "3") (pinfunction "3_3") (pintype "passive"))
      (node (ref "U$55") (pin "4") (pinfunction "4_4") (pintype "passive"))
      (node (ref "U$55") (pin "5") (pinfunction "5_5") (pintype "passive"))
    )
    (net (code "81") (name "Net-(U$56-Pad1)") (class "Default")
      (node (ref "U$56") (pin "1") (pinfunction "1_1") (pintype "passive"))
      (node (ref "U$56") (pin "2") (pinfunction "2_2") (pintype "passive"))
      (node (ref "U$56") (pin "3") (pinfunction "3_3") (pintype "passive"))
      (node (ref "U$56") (pin "4") (pinfunction "4_4") (pintype "passive"))
      (node (ref "U$56") (pin "5") (pinfunction "5_5") (pintype "passive"))
    )
    (net (code "82") (name "Net-(U$57-Pad1)") (class "Default")
      (node (ref "U$57") (pin "1") (pinfunction "1_1") (pintype "passive"))
      (node (ref "U$57") (pin "2") (pinfunction "2_2") (pintype "passive"))
      (node (ref "U$57") (pin "3") (pinfunction "3_3") (pintype "passive"))
      (node (ref "U$57") (pin "4") (pinfunction "4_4") (pintype "passive"))
      (node (ref "U$57") (pin "5") (pinfunction "5_5") (pintype "passive"))
    )
    (net (code "83") (name "Net-(U$58-Pad1)") (class "Default")
      (node (ref "U$58") (pin "1") (pinfunction "1_1") (pintype "passive"))
      (node (ref "U$58") (pin "2") (pinfunction "2_2") (pintype "passive"))
      (node (ref "U$58") (pin "3") (pinfunction "3_3") (pintype "passive"))
      (node (ref "U$58") (pin "4") (pinfunction "4_4") (pintype "passive"))
      (node (ref "U$58") (pin "5") (pinfunction "5_5") (pintype "passive"))
    )
    (net (code "84") (name "Net-(U$59-Pad1)") (class "Default")
      (node (ref "U$59") (pin "1") (pinfunction "1_1") (pintype "passive"))
      (node (ref "U$59") (pin "2") (pinfunction "2_2") (pintype "passive"))
      (node (ref "U$59") (pin "3") (pinfunction "3_3") (pintype "passive"))
      (node (ref "U$59") (pin "4") (pinfunction "4_4") (pintype "passive"))
      (node (ref "U$59") (pin "5") (pinfunction "5_5") (pintype "passive"))
    )
    (net (code "85") (name "unconnected-(U$11-Pad4.USBID)") (class "Default")
      (node (ref "U$11") (pin "4.USBID") (pinfunction "4.USBID_4.USBID") (pintype "bidirectional"))
    )
  )
)
